# Schem.net
KiCad netlist of a schematic drawn in Altium Designer
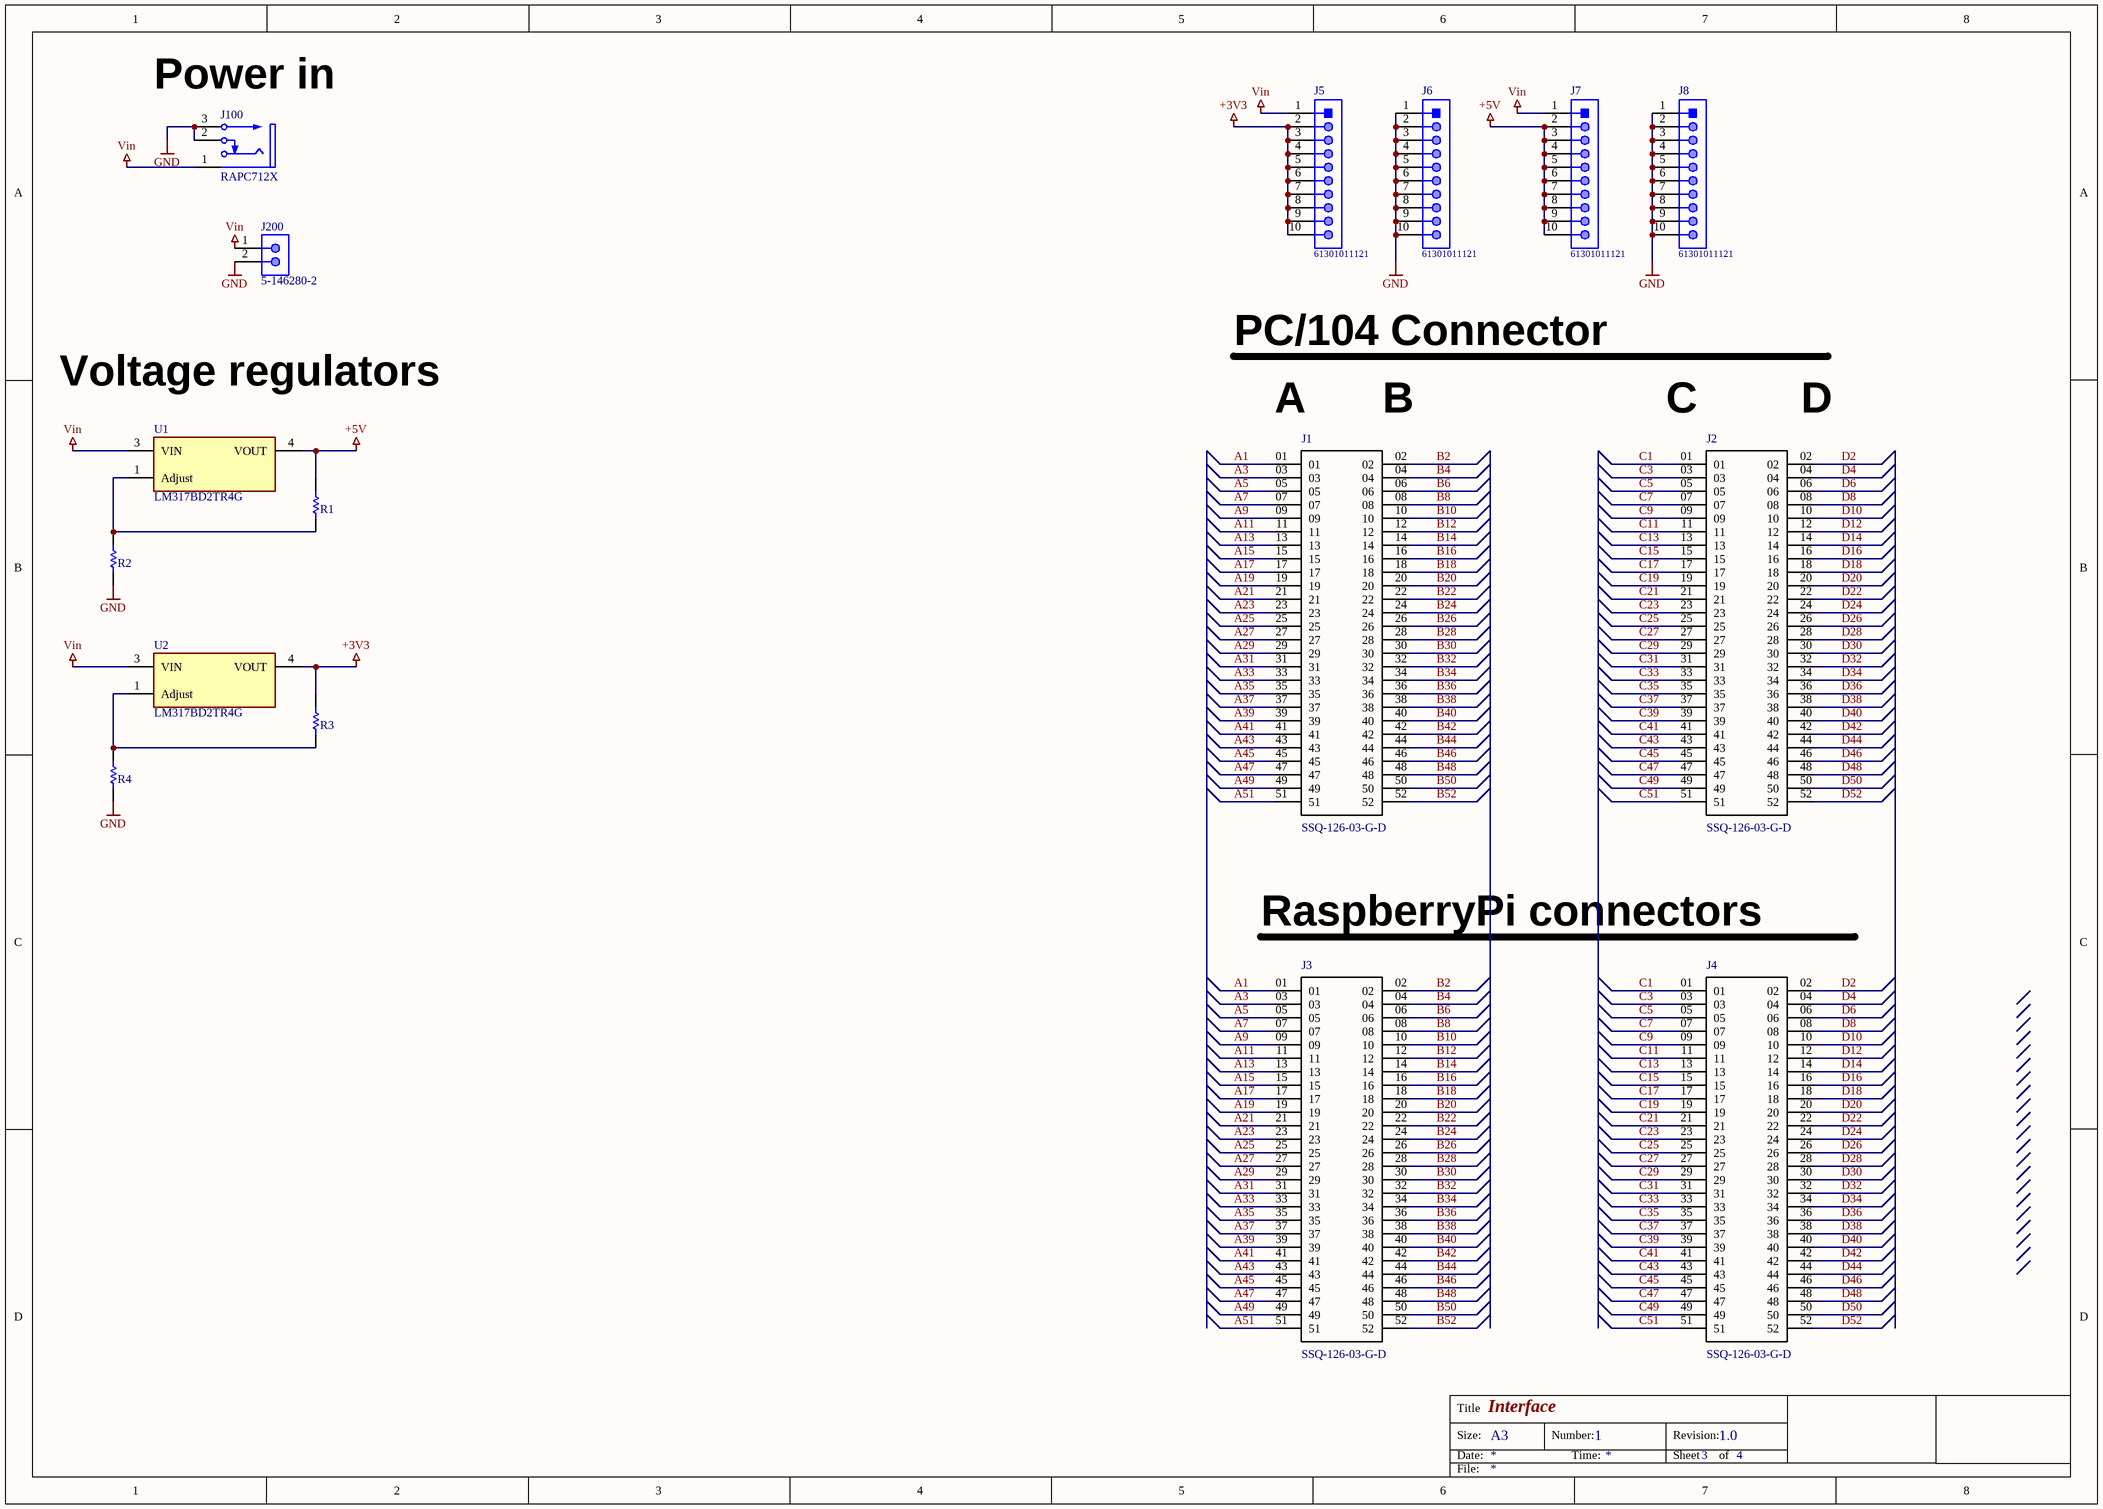
[diagram p0: Schem.SchDoc]

(export (version "E")
  (design (tool "Eeschema 10.0.6"))
  (components
    (comp (ref "J1")
      (value "SSQ-126-03-G-D")
      (footprint "*SAMTEC_SSQ-126-03-G-D_SSQ-126-03-G-D(Primary)")
      (libsource (lib "SSQ-126-03-G-D") (part "SSQ-126-03-G-D"))
    )
    (comp (ref "J2")
      (value "SSQ-126-03-G-D")
      (footprint "*SAMTEC_SSQ-126-03-G-D_SSQ-126-03-G-D(Primary)")
      (libsource (lib "SSQ-126-03-G-D") (part "SSQ-126-03-G-D"))
    )
    (comp (ref "J3")
      (value "SSQ-126-03-G-D")
      (footprint "*SAMTEC_SSQ-126-03-G-D_SSQ-126-03-G-D(Primary)")
      (libsource (lib "SSQ-126-03-G-D") (part "SSQ-126-03-G-D"))
    )
    (comp (ref "J4")
      (value "SSQ-126-03-G-D")
      (footprint "*SAMTEC_SSQ-126-03-G-D_SSQ-126-03-G-D(Primary)")
      (libsource (lib "SSQ-126-03-G-D") (part "SSQ-126-03-G-D"))
    )
    (comp (ref "J5")
      (value "61301011121")
      (footprint "61301011121")
      (description "THT Vertical Pin Header WR-PHD, Pitch 2.54 mm, Single Row, 10 pins")
      (fields (field (name "MANUFACTURER") "Wurth Elektronik") (field (name "PUBLISHER") "WurthElektronik"))
      (libsource (lib "Altium Content Vault") (part "WE-CN-1P-M-R10"))
    )
    (comp (ref "J6")
      (value "61301011121")
      (footprint "61301011121")
      (description "THT Vertical Pin Header WR-PHD, Pitch 2.54 mm, Single Row, 10 pins")
      (fields (field (name "MANUFACTURER") "Wurth Elektronik") (field (name "PUBLISHER") "WurthElektronik"))
      (libsource (lib "Altium Content Vault") (part "WE-CN-1P-M-R10"))
    )
    (comp (ref "J7")
      (value "61301011121")
      (footprint "61301011121")
      (description "THT Vertical Pin Header WR-PHD, Pitch 2.54 mm, Single Row, 10 pins")
      (fields (field (name "MANUFACTURER") "Wurth Elektronik") (field (name "PUBLISHER") "WurthElektronik"))
      (libsource (lib "Altium Content Vault") (part "WE-CN-1P-M-R10"))
    )
    (comp (ref "J8")
      (value "61301011121")
      (footprint "61301011121")
      (description "THT Vertical Pin Header WR-PHD, Pitch 2.54 mm, Single Row, 10 pins")
      (fields (field (name "MANUFACTURER") "Wurth Elektronik") (field (name "PUBLISHER") "WurthElektronik"))
      (libsource (lib "Altium Content Vault") (part "WE-CN-1P-M-R10"))
    )
    (comp (ref "J100")
      (value "RAPC712X")
      (footprint "SWITCH-RAPC712X-3_V")
      (description "Conn Powerjack Mini R/A PCMT, 5 A, 3-Pin THD, RoHS")
      (fields (field (name "MANUFACTURER") "Switchcraft"))
      (libsource (lib "Altium Content Vault") (part "SWITCH-RAPC712X-3"))
    )
    (comp (ref "J200")
      (value "5-146280-2")
      (footprint "TECO-5-146280-2_V")
      (fields (field (name "MANUFACTURER") "TE Connectivity"))
      (libsource (lib "Altium Content Vault") (part "CN-1P-M-R2"))
    )
    (comp (ref "R1")
      (value "CRCW12064K70FKEA")
      (footprint "RESC3216X60X45ML15T20")
      (description "Chip Resistor, 4.7 KOhm, +/- 1%, 0.25 W, -55 to 155 degC, 1206 (3216 Metric), RoHS, Tape and Reel")
      (fields (field (name "MANUFACTURER") "Vishay Semiconductor") (field (name "TOLERANCE") "1%"))
      (libsource (lib "Altium Content Vault") (part "RES-2"))
    )
    (comp (ref "R2")
      (value "CRCW12064K70FKEA")
      (footprint "RESC3216X60X45ML15T20")
      (description "Chip Resistor, 4.7 KOhm, +/- 1%, 0.25 W, -55 to 155 degC, 1206 (3216 Metric), RoHS, Tape and Reel")
      (fields (field (name "MANUFACTURER") "Vishay Semiconductor") (field (name "TOLERANCE") "1%"))
      (libsource (lib "Altium Content Vault") (part "RES-2"))
    )
    (comp (ref "R3")
      (value "CRCW12064K70FKEA")
      (footprint "RESC3216X60X45ML15T20")
      (description "Chip Resistor, 4.7 KOhm, +/- 1%, 0.25 W, -55 to 155 degC, 1206 (3216 Metric), RoHS, Tape and Reel")
      (fields (field (name "MANUFACTURER") "Vishay Semiconductor") (field (name "TOLERANCE") "1%"))
      (libsource (lib "Altium Content Vault") (part "RES-2"))
    )
    (comp (ref "R4")
      (value "CRCW12064K70FKEA")
      (footprint "RESC3216X60X45ML15T20")
      (description "Chip Resistor, 4.7 KOhm, +/- 1%, 0.25 W, -55 to 155 degC, 1206 (3216 Metric), RoHS, Tape and Reel")
      (fields (field (name "MANUFACTURER") "Vishay Semiconductor") (field (name "TOLERANCE") "1%"))
      (libsource (lib "Altium Content Vault") (part "RES-2"))
    )
    (comp (ref "U1")
      (value "LM317BD2TR4G")
      (footprint "FP-936-03-MFG")
      (description "IC REG LINEAR POS ADJ 1.5A D2PAK")
      (fields
        (field (name "MANUFACTURER") "ON Semiconductor")
        (field (name "OCTOPART") "https://octopart.com/lm317bd2tr4g-on+semiconductor-530493")
      )
      (libsource (lib "Altium Content Vault") (part "2cc77221438a5b2cc45cc30c3f51d25"))
    )
    (comp (ref "U2")
      (value "LM317BD2TR4G")
      (footprint "FP-936-03-MFG")
      (description "IC REG LINEAR POS ADJ 1.5A D2PAK")
      (fields
        (field (name "MANUFACTURER") "ON Semiconductor")
        (field (name "OCTOPART") "https://octopart.com/lm317bd2tr4g-on+semiconductor-530493")
      )
      (libsource (lib "Altium Content Vault") (part "2cc77221438a5b2cc45cc30c3f51d25"))
    )
  )
  (nets
    (net (code "1") (name "+3V3") (class "Default")
      (node (ref "J5") (pin "10") (pinfunction "10_10") (pintype "passive"))
      (node (ref "J5") (pin "2") (pinfunction "2_2") (pintype "passive"))
      (node (ref "J5") (pin "3") (pinfunction "3_3") (pintype "passive"))
      (node (ref "J5") (pin "4") (pinfunction "4_4") (pintype "passive"))
      (node (ref "J5") (pin "5") (pinfunction "5_5") (pintype "passive"))
      (node (ref "J5") (pin "6") (pinfunction "6_6") (pintype "passive"))
      (node (ref "J5") (pin "7") (pinfunction "7_7") (pintype "passive"))
      (node (ref "J5") (pin "8") (pinfunction "8_8") (pintype "passive"))
      (node (ref "J5") (pin "9") (pinfunction "9_9") (pintype "passive"))
      (node (ref "R3") (pin "2") (pinfunction "2_2") (pintype "passive"))
      (node (ref "U2") (pin "4") (pinfunction "VOUT_4") (pintype "power_in"))
    )
    (net (code "2") (name "+5V") (class "Default")
      (node (ref "J7") (pin "10") (pinfunction "10_10") (pintype "passive"))
      (node (ref "J7") (pin "2") (pinfunction "2_2") (pintype "passive"))
      (node (ref "J7") (pin "3") (pinfunction "3_3") (pintype "passive"))
      (node (ref "J7") (pin "4") (pinfunction "4_4") (pintype "passive"))
      (node (ref "J7") (pin "5") (pinfunction "5_5") (pintype "passive"))
      (node (ref "J7") (pin "6") (pinfunction "6_6") (pintype "passive"))
      (node (ref "J7") (pin "7") (pinfunction "7_7") (pintype "passive"))
      (node (ref "J7") (pin "8") (pinfunction "8_8") (pintype "passive"))
      (node (ref "J7") (pin "9") (pinfunction "9_9") (pintype "passive"))
      (node (ref "R1") (pin "2") (pinfunction "2_2") (pintype "passive"))
      (node (ref "U1") (pin "4") (pinfunction "VOUT_4") (pintype "power_in"))
    )
    (net (code "3") (name "/A1") (class "Default")
      (node (ref "J1") (pin "01") (pinfunction "01_01") (pintype "passive"))
      (node (ref "J3") (pin "01") (pinfunction "01_01") (pintype "passive"))
    )
    (net (code "4") (name "/A3") (class "Default")
      (node (ref "J1") (pin "03") (pinfunction "03_03") (pintype "passive"))
      (node (ref "J3") (pin "03") (pinfunction "03_03") (pintype "passive"))
    )
    (net (code "5") (name "/A5") (class "Default")
      (node (ref "J1") (pin "05") (pinfunction "05_05") (pintype "passive"))
      (node (ref "J3") (pin "05") (pinfunction "05_05") (pintype "passive"))
    )
    (net (code "6") (name "/A7") (class "Default")
      (node (ref "J1") (pin "07") (pinfunction "07_07") (pintype "passive"))
      (node (ref "J3") (pin "07") (pinfunction "07_07") (pintype "passive"))
    )
    (net (code "7") (name "/A9") (class "Default")
      (node (ref "J1") (pin "09") (pinfunction "09_09") (pintype "passive"))
      (node (ref "J3") (pin "09") (pinfunction "09_09") (pintype "passive"))
    )
    (net (code "8") (name "/A11") (class "Default")
      (node (ref "J1") (pin "11") (pinfunction "11_11") (pintype "passive"))
      (node (ref "J3") (pin "11") (pinfunction "11_11") (pintype "passive"))
    )
    (net (code "9") (name "/A13") (class "Default")
      (node (ref "J1") (pin "13") (pinfunction "13_13") (pintype "passive"))
      (node (ref "J3") (pin "13") (pinfunction "13_13") (pintype "passive"))
    )
    (net (code "10") (name "/A15") (class "Default")
      (node (ref "J1") (pin "15") (pinfunction "15_15") (pintype "passive"))
      (node (ref "J3") (pin "15") (pinfunction "15_15") (pintype "passive"))
    )
    (net (code "11") (name "/A17") (class "Default")
      (node (ref "J1") (pin "17") (pinfunction "17_17") (pintype "passive"))
      (node (ref "J3") (pin "17") (pinfunction "17_17") (pintype "passive"))
    )
    (net (code "12") (name "/A19") (class "Default")
      (node (ref "J1") (pin "19") (pinfunction "19_19") (pintype "passive"))
      (node (ref "J3") (pin "19") (pinfunction "19_19") (pintype "passive"))
    )
    (net (code "13") (name "/A21") (class "Default")
      (node (ref "J1") (pin "21") (pinfunction "21_21") (pintype "passive"))
      (node (ref "J3") (pin "21") (pinfunction "21_21") (pintype "passive"))
    )
    (net (code "14") (name "/A23") (class "Default")
      (node (ref "J1") (pin "23") (pinfunction "23_23") (pintype "passive"))
      (node (ref "J3") (pin "23") (pinfunction "23_23") (pintype "passive"))
    )
    (net (code "15") (name "/A25") (class "Default")
      (node (ref "J1") (pin "25") (pinfunction "25_25") (pintype "passive"))
      (node (ref "J3") (pin "25") (pinfunction "25_25") (pintype "passive"))
    )
    (net (code "16") (name "/A27") (class "Default")
      (node (ref "J1") (pin "27") (pinfunction "27_27") (pintype "passive"))
      (node (ref "J3") (pin "27") (pinfunction "27_27") (pintype "passive"))
    )
    (net (code "17") (name "/A29") (class "Default")
      (node (ref "J1") (pin "29") (pinfunction "29_29") (pintype "passive"))
      (node (ref "J3") (pin "29") (pinfunction "29_29") (pintype "passive"))
    )
    (net (code "18") (name "/A31") (class "Default")
      (node (ref "J1") (pin "31") (pinfunction "31_31") (pintype "passive"))
      (node (ref "J3") (pin "31") (pinfunction "31_31") (pintype "passive"))
    )
    (net (code "19") (name "/A33") (class "Default")
      (node (ref "J1") (pin "33") (pinfunction "33_33") (pintype "passive"))
      (node (ref "J3") (pin "33") (pinfunction "33_33") (pintype "passive"))
    )
    (net (code "20") (name "/A35") (class "Default")
      (node (ref "J1") (pin "35") (pinfunction "35_35") (pintype "passive"))
      (node (ref "J3") (pin "35") (pinfunction "35_35") (pintype "passive"))
    )
    (net (code "21") (name "/A37") (class "Default")
      (node (ref "J1") (pin "37") (pinfunction "37_37") (pintype "passive"))
      (node (ref "J3") (pin "37") (pinfunction "37_37") (pintype "passive"))
    )
    (net (code "22") (name "/A39") (class "Default")
      (node (ref "J1") (pin "39") (pinfunction "39_39") (pintype "passive"))
      (node (ref "J3") (pin "39") (pinfunction "39_39") (pintype "passive"))
    )
    (net (code "23") (name "/A41") (class "Default")
      (node (ref "J1") (pin "41") (pinfunction "41_41") (pintype "passive"))
      (node (ref "J3") (pin "41") (pinfunction "41_41") (pintype "passive"))
    )
    (net (code "24") (name "/A43") (class "Default")
      (node (ref "J1") (pin "43") (pinfunction "43_43") (pintype "passive"))
      (node (ref "J3") (pin "43") (pinfunction "43_43") (pintype "passive"))
    )
    (net (code "25") (name "/A45") (class "Default")
      (node (ref "J1") (pin "45") (pinfunction "45_45") (pintype "passive"))
      (node (ref "J3") (pin "45") (pinfunction "45_45") (pintype "passive"))
    )
    (net (code "26") (name "/A47") (class "Default")
      (node (ref "J1") (pin "47") (pinfunction "47_47") (pintype "passive"))
      (node (ref "J3") (pin "47") (pinfunction "47_47") (pintype "passive"))
    )
    (net (code "27") (name "/A49") (class "Default")
      (node (ref "J1") (pin "49") (pinfunction "49_49") (pintype "passive"))
      (node (ref "J3") (pin "49") (pinfunction "49_49") (pintype "passive"))
    )
    (net (code "28") (name "/A51") (class "Default")
      (node (ref "J1") (pin "51") (pinfunction "51_51") (pintype "passive"))
      (node (ref "J3") (pin "51") (pinfunction "51_51") (pintype "passive"))
    )
    (net (code "29") (name "/B2") (class "Default")
      (node (ref "J1") (pin "02") (pinfunction "02_02") (pintype "passive"))
      (node (ref "J3") (pin "02") (pinfunction "02_02") (pintype "passive"))
    )
    (net (code "30") (name "/B4") (class "Default")
      (node (ref "J1") (pin "04") (pinfunction "04_04") (pintype "passive"))
      (node (ref "J3") (pin "04") (pinfunction "04_04") (pintype "passive"))
    )
    (net (code "31") (name "/B6") (class "Default")
      (node (ref "J1") (pin "06") (pinfunction "06_06") (pintype "passive"))
      (node (ref "J3") (pin "06") (pinfunction "06_06") (pintype "passive"))
    )
    (net (code "32") (name "/B8") (class "Default")
      (node (ref "J1") (pin "08") (pinfunction "08_08") (pintype "passive"))
      (node (ref "J3") (pin "08") (pinfunction "08_08") (pintype "passive"))
    )
    (net (code "33") (name "/B10") (class "Default")
      (node (ref "J1") (pin "10") (pinfunction "10_10") (pintype "passive"))
      (node (ref "J3") (pin "10") (pinfunction "10_10") (pintype "passive"))
    )
    (net (code "34") (name "/B12") (class "Default")
      (node (ref "J1") (pin "12") (pinfunction "12_12") (pintype "passive"))
      (node (ref "J3") (pin "12") (pinfunction "12_12") (pintype "passive"))
    )
    (net (code "35") (name "/B14") (class "Default")
      (node (ref "J1") (pin "14") (pinfunction "14_14") (pintype "passive"))
      (node (ref "J3") (pin "14") (pinfunction "14_14") (pintype "passive"))
    )
    (net (code "36") (name "/B16") (class "Default")
      (node (ref "J1") (pin "16") (pinfunction "16_16") (pintype "passive"))
      (node (ref "J3") (pin "16") (pinfunction "16_16") (pintype "passive"))
    )
    (net (code "37") (name "/B18") (class "Default")
      (node (ref "J1") (pin "18") (pinfunction "18_18") (pintype "passive"))
      (node (ref "J3") (pin "18") (pinfunction "18_18") (pintype "passive"))
    )
    (net (code "38") (name "/B20") (class "Default")
      (node (ref "J1") (pin "20") (pinfunction "20_20") (pintype "passive"))
      (node (ref "J3") (pin "20") (pinfunction "20_20") (pintype "passive"))
    )
    (net (code "39") (name "/B22") (class "Default")
      (node (ref "J1") (pin "22") (pinfunction "22_22") (pintype "passive"))
      (node (ref "J3") (pin "22") (pinfunction "22_22") (pintype "passive"))
    )
    (net (code "40") (name "/B24") (class "Default")
      (node (ref "J1") (pin "24") (pinfunction "24_24") (pintype "passive"))
      (node (ref "J3") (pin "24") (pinfunction "24_24") (pintype "passive"))
    )
    (net (code "41") (name "/B26") (class "Default")
      (node (ref "J1") (pin "26") (pinfunction "26_26") (pintype "passive"))
      (node (ref "J3") (pin "26") (pinfunction "26_26") (pintype "passive"))
    )
    (net (code "42") (name "/B28") (class "Default")
      (node (ref "J1") (pin "28") (pinfunction "28_28") (pintype "passive"))
      (node (ref "J3") (pin "28") (pinfunction "28_28") (pintype "passive"))
    )
    (net (code "43") (name "/B30") (class "Default")
      (node (ref "J1") (pin "30") (pinfunction "30_30") (pintype "passive"))
      (node (ref "J3") (pin "30") (pinfunction "30_30") (pintype "passive"))
    )
    (net (code "44") (name "/B32") (class "Default")
      (node (ref "J1") (pin "32") (pinfunction "32_32") (pintype "passive"))
      (node (ref "J3") (pin "32") (pinfunction "32_32") (pintype "passive"))
    )
    (net (code "45") (name "/B34") (class "Default")
      (node (ref "J1") (pin "34") (pinfunction "34_34") (pintype "passive"))
      (node (ref "J3") (pin "34") (pinfunction "34_34") (pintype "passive"))
    )
    (net (code "46") (name "/B36") (class "Default")
      (node (ref "J1") (pin "36") (pinfunction "36_36") (pintype "passive"))
      (node (ref "J3") (pin "36") (pinfunction "36_36") (pintype "passive"))
    )
    (net (code "47") (name "/B38") (class "Default")
      (node (ref "J1") (pin "38") (pinfunction "38_38") (pintype "passive"))
      (node (ref "J3") (pin "38") (pinfunction "38_38") (pintype "passive"))
    )
    (net (code "48") (name "/B40") (class "Default")
      (node (ref "J1") (pin "40") (pinfunction "40_40") (pintype "passive"))
      (node (ref "J3") (pin "40") (pinfunction "40_40") (pintype "passive"))
    )
    (net (code "49") (name "/B42") (class "Default")
      (node (ref "J1") (pin "42") (pinfunction "42_42") (pintype "passive"))
      (node (ref "J3") (pin "42") (pinfunction "42_42") (pintype "passive"))
    )
    (net (code "50") (name "/B44") (class "Default")
      (node (ref "J1") (pin "44") (pinfunction "44_44") (pintype "passive"))
      (node (ref "J3") (pin "44") (pinfunction "44_44") (pintype "passive"))
    )
    (net (code "51") (name "/B46") (class "Default")
      (node (ref "J1") (pin "46") (pinfunction "46_46") (pintype "passive"))
      (node (ref "J3") (pin "46") (pinfunction "46_46") (pintype "passive"))
    )
    (net (code "52") (name "/B48") (class "Default")
      (node (ref "J1") (pin "48") (pinfunction "48_48") (pintype "passive"))
      (node (ref "J3") (pin "48") (pinfunction "48_48") (pintype "passive"))
    )
    (net (code "53") (name "/B50") (class "Default")
      (node (ref "J1") (pin "50") (pinfunction "50_50") (pintype "passive"))
      (node (ref "J3") (pin "50") (pinfunction "50_50") (pintype "passive"))
    )
    (net (code "54") (name "/B52") (class "Default")
      (node (ref "J1") (pin "52") (pinfunction "52_52") (pintype "passive"))
      (node (ref "J3") (pin "52") (pinfunction "52_52") (pintype "passive"))
    )
    (net (code "55") (name "/C1") (class "Default")
      (node (ref "J2") (pin "01") (pinfunction "01_01") (pintype "passive"))
      (node (ref "J4") (pin "01") (pinfunction "01_01") (pintype "passive"))
    )
    (net (code "56") (name "/C3") (class "Default")
      (node (ref "J2") (pin "03") (pinfunction "03_03") (pintype "passive"))
      (node (ref "J4") (pin "03") (pinfunction "03_03") (pintype "passive"))
    )
    (net (code "57") (name "/C5") (class "Default")
      (node (ref "J2") (pin "05") (pinfunction "05_05") (pintype "passive"))
      (node (ref "J4") (pin "05") (pinfunction "05_05") (pintype "passive"))
    )
    (net (code "58") (name "/C7") (class "Default")
      (node (ref "J2") (pin "07") (pinfunction "07_07") (pintype "passive"))
      (node (ref "J4") (pin "07") (pinfunction "07_07") (pintype "passive"))
    )
    (net (code "59") (name "/C9") (class "Default")
      (node (ref "J2") (pin "09") (pinfunction "09_09") (pintype "passive"))
      (node (ref "J4") (pin "09") (pinfunction "09_09") (pintype "passive"))
    )
    (net (code "60") (name "/C11") (class "Default")
      (node (ref "J2") (pin "11") (pinfunction "11_11") (pintype "passive"))
      (node (ref "J4") (pin "11") (pinfunction "11_11") (pintype "passive"))
    )
    (net (code "61") (name "/C13") (class "Default")
      (node (ref "J2") (pin "13") (pinfunction "13_13") (pintype "passive"))
      (node (ref "J4") (pin "13") (pinfunction "13_13") (pintype "passive"))
    )
    (net (code "62") (name "/C15") (class "Default")
      (node (ref "J2") (pin "15") (pinfunction "15_15") (pintype "passive"))
      (node (ref "J4") (pin "15") (pinfunction "15_15") (pintype "passive"))
    )
    (net (code "63") (name "/C17") (class "Default")
      (node (ref "J2") (pin "17") (pinfunction "17_17") (pintype "passive"))
      (node (ref "J4") (pin "17") (pinfunction "17_17") (pintype "passive"))
    )
    (net (code "64") (name "/C19") (class "Default")
      (node (ref "J2") (pin "19") (pinfunction "19_19") (pintype "passive"))
      (node (ref "J4") (pin "19") (pinfunction "19_19") (pintype "passive"))
    )
    (net (code "65") (name "/C21") (class "Default")
      (node (ref "J2") (pin "21") (pinfunction "21_21") (pintype "passive"))
      (node (ref "J4") (pin "21") (pinfunction "21_21") (pintype "passive"))
    )
    (net (code "66") (name "/C23") (class "Default")
      (node (ref "J2") (pin "23") (pinfunction "23_23") (pintype "passive"))
      (node (ref "J4") (pin "23") (pinfunction "23_23") (pintype "passive"))
    )
    (net (code "67") (name "/C25") (class "Default")
      (node (ref "J2") (pin "25") (pinfunction "25_25") (pintype "passive"))
      (node (ref "J4") (pin "25") (pinfunction "25_25") (pintype "passive"))
    )
    (net (code "68") (name "/C27") (class "Default")
      (node (ref "J2") (pin "27") (pinfunction "27_27") (pintype "passive"))
      (node (ref "J4") (pin "27") (pinfunction "27_27") (pintype "passive"))
    )
    (net (code "69") (name "/C29") (class "Default")
      (node (ref "J2") (pin "29") (pinfunction "29_29") (pintype "passive"))
      (node (ref "J4") (pin "29") (pinfunction "29_29") (pintype "passive"))
    )
    (net (code "70") (name "/C31") (class "Default")
      (node (ref "J2") (pin "31") (pinfunction "31_31") (pintype "passive"))
      (node (ref "J4") (pin "31") (pinfunction "31_31") (pintype "passive"))
    )
    (net (code "71") (name "/C33") (class "Default")
      (node (ref "J2") (pin "33") (pinfunction "33_33") (pintype "passive"))
      (node (ref "J4") (pin "33") (pinfunction "33_33") (pintype "passive"))
    )
    (net (code "72") (name "/C35") (class "Default")
      (node (ref "J2") (pin "35") (pinfunction "35_35") (pintype "passive"))
      (node (ref "J4") (pin "35") (pinfunction "35_35") (pintype "passive"))
    )
    (net (code "73") (name "/C37") (class "Default")
      (node (ref "J2") (pin "37") (pinfunction "37_37") (pintype "passive"))
      (node (ref "J4") (pin "37") (pinfunction "37_37") (pintype "passive"))
    )
    (net (code "74") (name "/C39") (class "Default")
      (node (ref "J2") (pin "39") (pinfunction "39_39") (pintype "passive"))
      (node (ref "J4") (pin "39") (pinfunction "39_39") (pintype "passive"))
    )
    (net (code "75") (name "/C41") (class "Default")
      (node (ref "J2") (pin "41") (pinfunction "41_41") (pintype "passive"))
      (node (ref "J4") (pin "41") (pinfunction "41_41") (pintype "passive"))
    )
    (net (code "76") (name "/C43") (class "Default")
      (node (ref "J2") (pin "43") (pinfunction "43_43") (pintype "passive"))
      (node (ref "J4") (pin "43") (pinfunction "43_43") (pintype "passive"))
    )
    (net (code "77") (name "/C45") (class "Default")
      (node (ref "J2") (pin "45") (pinfunction "45_45") (pintype "passive"))
      (node (ref "J4") (pin "45") (pinfunction "45_45") (pintype "passive"))
    )
    (net (code "78") (name "/C47") (class "Default")
      (node (ref "J2") (pin "47") (pinfunction "47_47") (pintype "passive"))
      (node (ref "J4") (pin "47") (pinfunction "47_47") (pintype "passive"))
    )
    (net (code "79") (name "/C49") (class "Default")
      (node (ref "J2") (pin "49") (pinfunction "49_49") (pintype "passive"))
      (node (ref "J4") (pin "49") (pinfunction "49_49") (pintype "passive"))
    )
    (net (code "80") (name "/C51") (class "Default")
      (node (ref "J2") (pin "51") (pinfunction "51_51") (pintype "passive"))
      (node (ref "J4") (pin "51") (pinfunction "51_51") (pintype "passive"))
    )
    (net (code "81") (name "/D2") (class "Default")
      (node (ref "J2") (pin "02") (pinfunction "02_02") (pintype "passive"))
      (node (ref "J4") (pin "02") (pinfunction "02_02") (pintype "passive"))
    )
    (net (code "82") (name "/D4") (class "Default")
      (node (ref "J2") (pin "04") (pinfunction "04_04") (pintype "passive"))
      (node (ref "J4") (pin "04") (pinfunction "04_04") (pintype "passive"))
    )
    (net (code "83") (name "/D6") (class "Default")
      (node (ref "J2") (pin "06") (pinfunction "06_06") (pintype "passive"))
      (node (ref "J4") (pin "06") (pinfunction "06_06") (pintype "passive"))
    )
    (net (code "84") (name "/D8") (class "Default")
      (node (ref "J2") (pin "08") (pinfunction "08_08") (pintype "passive"))
      (node (ref "J4") (pin "08") (pinfunction "08_08") (pintype "passive"))
    )
    (net (code "85") (name "/D10") (class "Default")
      (node (ref "J2") (pin "10") (pinfunction "10_10") (pintype "passive"))
      (node (ref "J4") (pin "10") (pinfunction "10_10") (pintype "passive"))
    )
    (net (code "86") (name "/D12") (class "Default")
      (node (ref "J2") (pin "12") (pinfunction "12_12") (pintype "passive"))
      (node (ref "J4") (pin "12") (pinfunction "12_12") (pintype "passive"))
    )
    (net (code "87") (name "/D14") (class "Default")
      (node (ref "J2") (pin "14") (pinfunction "14_14") (pintype "passive"))
      (node (ref "J4") (pin "14") (pinfunction "14_14") (pintype "passive"))
    )
    (net (code "88") (name "/D16") (class "Default")
      (node (ref "J2") (pin "16") (pinfunction "16_16") (pintype "passive"))
      (node (ref "J4") (pin "16") (pinfunction "16_16") (pintype "passive"))
    )
    (net (code "89") (name "/D18") (class "Default")
      (node (ref "J2") (pin "18") (pinfunction "18_18") (pintype "passive"))
      (node (ref "J4") (pin "18") (pinfunction "18_18") (pintype "passive"))
    )
    (net (code "90") (name "/D20") (class "Default")
      (node (ref "J2") (pin "20") (pinfunction "20_20") (pintype "passive"))
      (node (ref "J4") (pin "20") (pinfunction "20_20") (pintype "passive"))
    )
    (net (code "91") (name "/D22") (class "Default")
      (node (ref "J2") (pin "22") (pinfunction "22_22") (pintype "passive"))
      (node (ref "J4") (pin "22") (pinfunction "22_22") (pintype "passive"))
    )
    (net (code "92") (name "/D24") (class "Default")
      (node (ref "J2") (pin "24") (pinfunction "24_24") (pintype "passive"))
      (node (ref "J4") (pin "24") (pinfunction "24_24") (pintype "passive"))
    )
    (net (code "93") (name "/D26") (class "Default")
      (node (ref "J2") (pin "26") (pinfunction "26_26") (pintype "passive"))
      (node (ref "J4") (pin "26") (pinfunction "26_26") (pintype "passive"))
    )
    (net (code "94") (name "/D28") (class "Default")
      (node (ref "J2") (pin "28") (pinfunction "28_28") (pintype "passive"))
      (node (ref "J4") (pin "28") (pinfunction "28_28") (pintype "passive"))
    )
    (net (code "95") (name "/D30") (class "Default")
      (node (ref "J2") (pin "30") (pinfunction "30_30") (pintype "passive"))
      (node (ref "J4") (pin "30") (pinfunction "30_30") (pintype "passive"))
    )
    (net (code "96") (name "/D32") (class "Default")
      (node (ref "J2") (pin "32") (pinfunction "32_32") (pintype "passive"))
      (node (ref "J4") (pin "32") (pinfunction "32_32") (pintype "passive"))
    )
    (net (code "97") (name "/D34") (class "Default")
      (node (ref "J2") (pin "34") (pinfunction "34_34") (pintype "passive"))
      (node (ref "J4") (pin "34") (pinfunction "34_34") (pintype "passive"))
    )
    (net (code "98") (name "/D36") (class "Default")
      (node (ref "J2") (pin "36") (pinfunction "36_36") (pintype "passive"))
      (node (ref "J4") (pin "36") (pinfunction "36_36") (pintype "passive"))
    )
    (net (code "99") (name "/D38") (class "Default")
      (node (ref "J2") (pin "38") (pinfunction "38_38") (pintype "passive"))
      (node (ref "J4") (pin "38") (pinfunction "38_38") (pintype "passive"))
    )
    (net (code "100") (name "/D40") (class "Default")
      (node (ref "J2") (pin "40") (pinfunction "40_40") (pintype "passive"))
      (node (ref "J4") (pin "40") (pinfunction "40_40") (pintype "passive"))
    )
    (net (code "101") (name "/D42") (class "Default")
      (node (ref "J2") (pin "42") (pinfunction "42_42") (pintype "passive"))
      (node (ref "J4") (pin "42") (pinfunction "42_42") (pintype "passive"))
    )
    (net (code "102") (name "/D44") (class "Default")
      (node (ref "J2") (pin "44") (pinfunction "44_44") (pintype "passive"))
      (node (ref "J4") (pin "44") (pinfunction "44_44") (pintype "passive"))
    )
    (net (code "103") (name "/D46") (class "Default")
      (node (ref "J2") (pin "46") (pinfunction "46_46") (pintype "passive"))
      (node (ref "J4") (pin "46") (pinfunction "46_46") (pintype "passive"))
    )
    (net (code "104") (name "/D48") (class "Default")
      (node (ref "J2") (pin "48") (pinfunction "48_48") (pintype "passive"))
      (node (ref "J4") (pin "48") (pinfunction "48_48") (pintype "passive"))
    )
    (net (code "105") (name "/D50") (class "Default")
      (node (ref "J2") (pin "50") (pinfunction "50_50") (pintype "passive"))
      (node (ref "J4") (pin "50") (pinfunction "50_50") (pintype "passive"))
    )
    (net (code "106") (name "/D52") (class "Default")
      (node (ref "J2") (pin "52") (pinfunction "52_52") (pintype "passive"))
      (node (ref "J4") (pin "52") (pinfunction "52_52") (pintype "passive"))
    )
    (net (code "107") (name "GND") (class "Default")
      (node (ref "J100") (pin "2") (pinfunction "2_2") (pintype "passive"))
      (node (ref "J100") (pin "3") (pinfunction "3_3") (pintype "passive"))
      (node (ref "J200") (pin "2") (pinfunction "2_2") (pintype "passive"))
      (node (ref "J6") (pin "1") (pinfunction "1_1") (pintype "passive"))
      (node (ref "J6") (pin "10") (pinfunction "10_10") (pintype "passive"))
      (node (ref "J6") (pin "2") (pinfunction "2_2") (pintype "passive"))
      (node (ref "J6") (pin "3") (pinfunction "3_3") (pintype "passive"))
      (node (ref "J6") (pin "4") (pinfunction "4_4") (pintype "passive"))
      (node (ref "J6") (pin "5") (pinfunction "5_5") (pintype "passive"))
      (node (ref "J6") (pin "6") (pinfunction "6_6") (pintype "passive"))
      (node (ref "J6") (pin "7") (pinfunction "7_7") (pintype "passive"))
      (node (ref "J6") (pin "8") (pinfunction "8_8") (pintype "passive"))
      (node (ref "J6") (pin "9") (pinfunction "9_9") (pintype "passive"))
      (node (ref "J8") (pin "1") (pinfunction "1_1") (pintype "passive"))
      (node (ref "J8") (pin "10") (pinfunction "10_10") (pintype "passive"))
      (node (ref "J8") (pin "2") (pinfunction "2_2") (pintype "passive"))
      (node (ref "J8") (pin "3") (pinfunction "3_3") (pintype "passive"))
      (node (ref "J8") (pin "4") (pinfunction "4_4") (pintype "passive"))
      (node (ref "J8") (pin "5") (pinfunction "5_5") (pintype "passive"))
      (node (ref "J8") (pin "6") (pinfunction "6_6") (pintype "passive"))
      (node (ref "J8") (pin "7") (pinfunction "7_7") (pintype "passive"))
      (node (ref "J8") (pin "8") (pinfunction "8_8") (pintype "passive"))
      (node (ref "J8") (pin "9") (pinfunction "9_9") (pintype "passive"))
      (node (ref "R2") (pin "1") (pinfunction "1_1") (pintype "passive"))
      (node (ref "R4") (pin "1") (pinfunction "1_1") (pintype "passive"))
    )
    (net (code "108") (name "Net-(U1-Adjust)") (class "Default")
      (node (ref "R1") (pin "1") (pinfunction "1_1") (pintype "passive"))
      (node (ref "R2") (pin "2") (pinfunction "2_2") (pintype "passive"))
      (node (ref "U1") (pin "1") (pinfunction "Adjust_1") (pintype "passive"))
    )
    (net (code "109") (name "Net-(U2-Adjust)") (class "Default")
      (node (ref "R3") (pin "1") (pinfunction "1_1") (pintype "passive"))
      (node (ref "R4") (pin "2") (pinfunction "2_2") (pintype "passive"))
      (node (ref "U2") (pin "1") (pinfunction "Adjust_1") (pintype "passive"))
    )
    (net (code "110") (name "Vin") (class "Default")
      (node (ref "J100") (pin "1") (pinfunction "1_1") (pintype "passive"))
      (node (ref "J200") (pin "1") (pinfunction "1_1") (pintype "passive"))
      (node (ref "J5") (pin "1") (pinfunction "1_1") (pintype "passive"))
      (node (ref "J7") (pin "1") (pinfunction "1_1") (pintype "passive"))
      (node (ref "U1") (pin "3") (pinfunction "VIN_3") (pintype "power_in"))
      (node (ref "U2") (pin "3") (pinfunction "VIN_3") (pintype "power_in"))
    )
  )
)
